# TF0060DCA.net
KiCad netlist of a schematic drawn in EAGLE
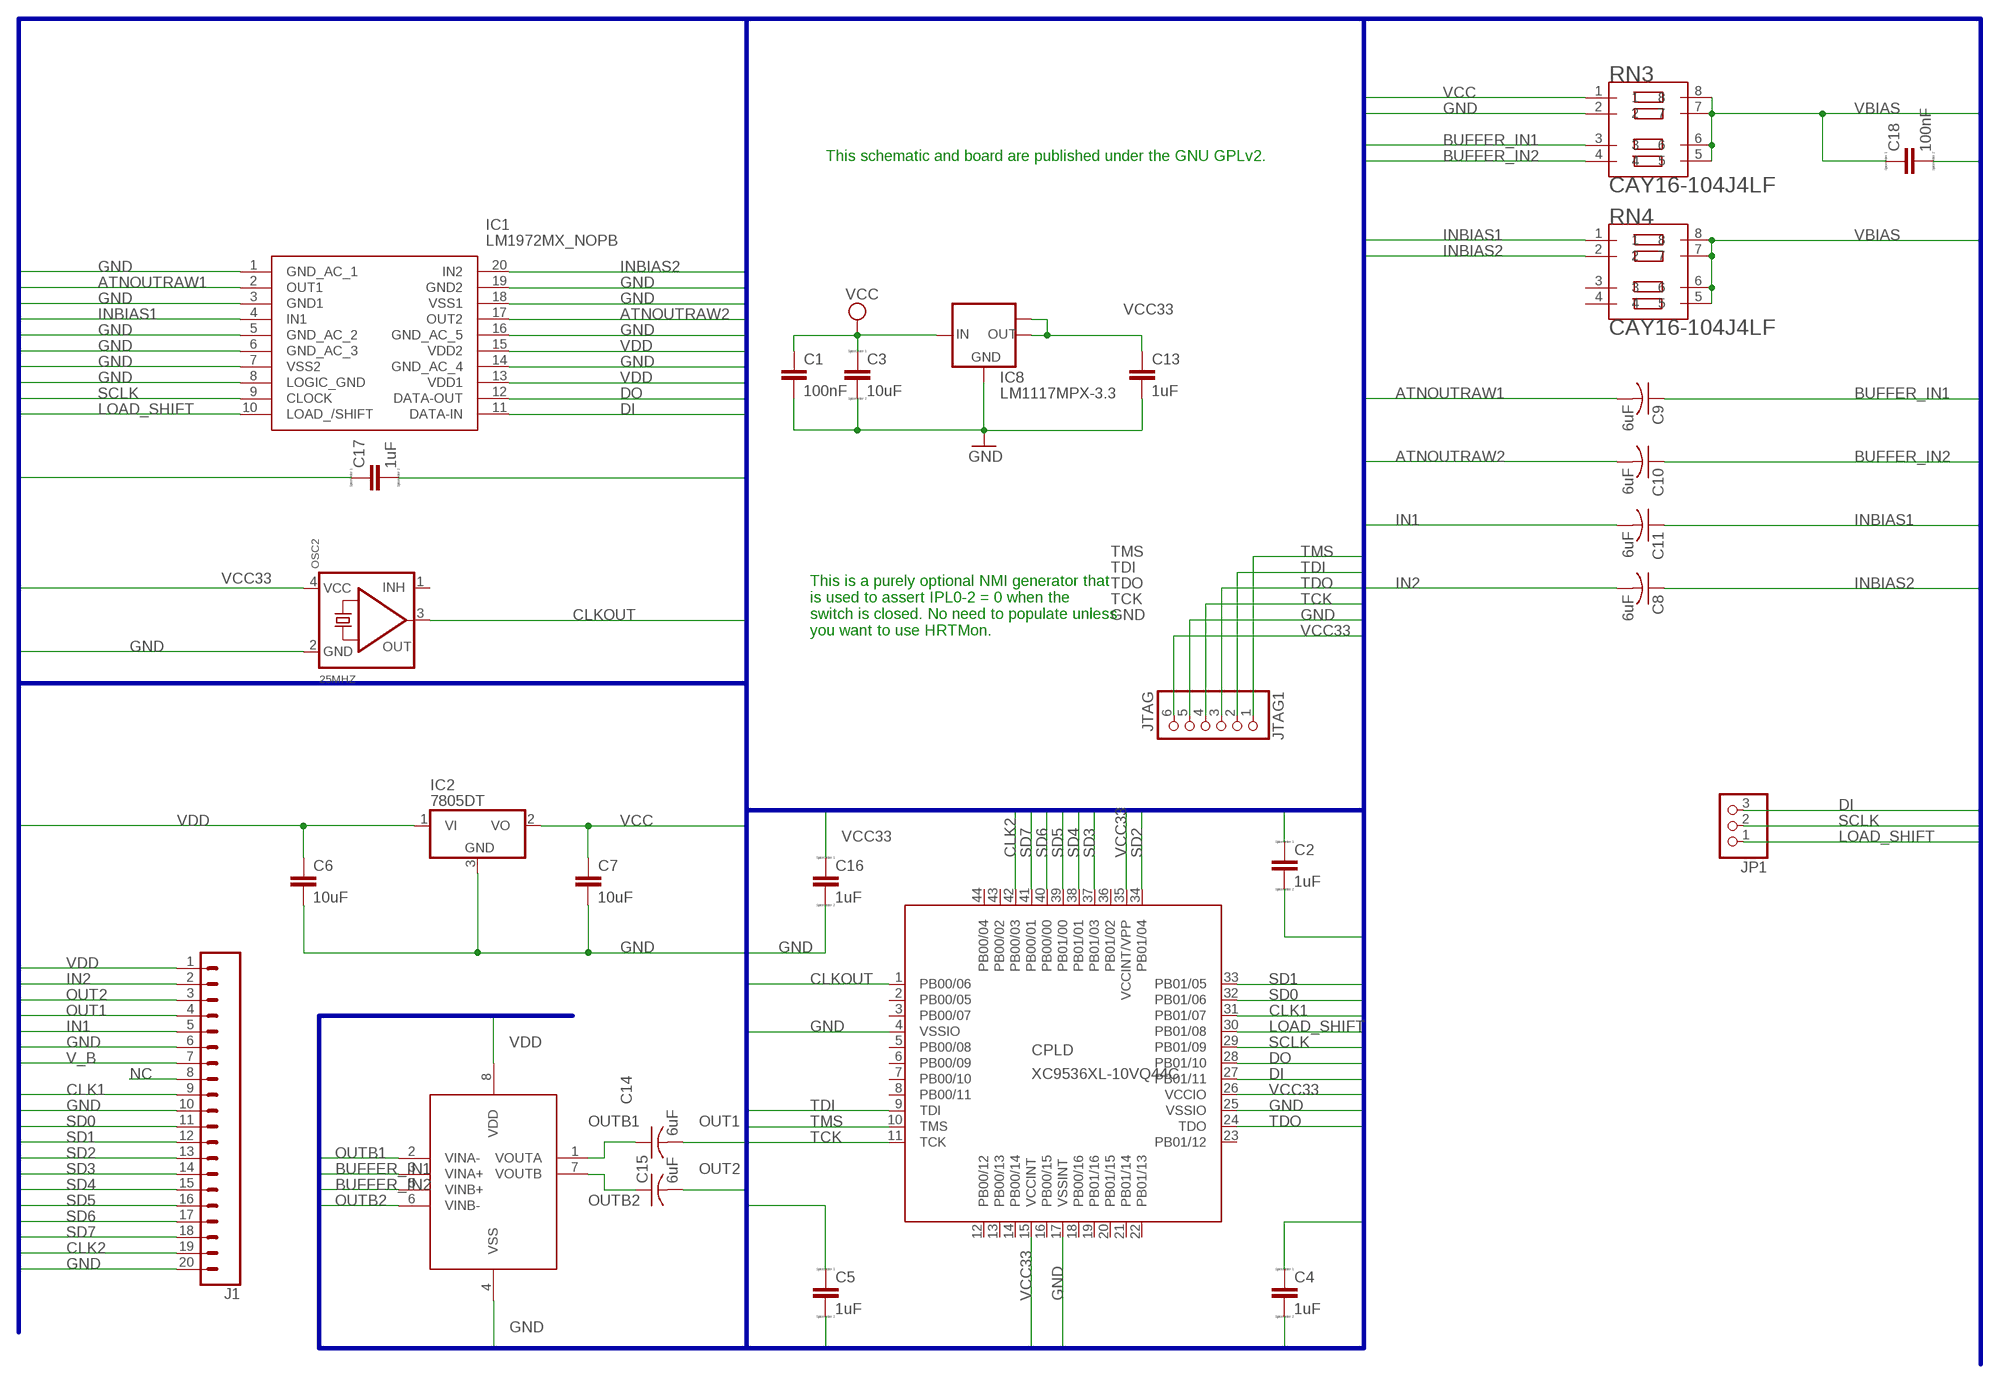
[diagram p0: schematic, sheet 1]

(export (version "E")
  (design (tool "Eeschema 10.0.6"))
  (components
    (comp (ref "C1")
      (value "100nF")
      (footprint "eagle-import:C1206")
      (libsource (lib "eagle-import") (part "C-EUC1206"))
    )
    (comp (ref "C2")
      (value "1uF")
      (footprint "eagle-import:C0603")
      (libsource (lib "eagle-import") (part "CC0603"))
    )
    (comp (ref "C3")
      (value "10uF")
      (footprint "eagle-import:C0603")
      (libsource (lib "eagle-import") (part "CC0603"))
    )
    (comp (ref "C4")
      (value "1uF")
      (footprint "eagle-import:C0603")
      (libsource (lib "eagle-import") (part "CC0603"))
    )
    (comp (ref "C5")
      (value "1uF")
      (footprint "eagle-import:C0603")
      (libsource (lib "eagle-import") (part "CC0603"))
    )
    (comp (ref "C6")
      (value "10uF")
      (footprint "eagle-import:C1206")
      (libsource (lib "eagle-import") (part "C-EUC1206"))
    )
    (comp (ref "C7")
      (value "10uF")
      (footprint "eagle-import:C1206")
      (libsource (lib "eagle-import") (part "C-EUC1206"))
    )
    (comp (ref "C8")
      (value "6uF")
      (footprint "eagle-import:C0805")
      (libsource (lib "eagle-import") (part "C-USC0805"))
    )
    (comp (ref "C9")
      (value "6uF")
      (footprint "eagle-import:C0805")
      (libsource (lib "eagle-import") (part "C-USC0805"))
    )
    (comp (ref "C10")
      (value "6uF")
      (footprint "eagle-import:C0805")
      (libsource (lib "eagle-import") (part "C-USC0805"))
    )
    (comp (ref "C11")
      (value "6uF")
      (footprint "eagle-import:C0805")
      (libsource (lib "eagle-import") (part "C-USC0805"))
    )
    (comp (ref "C13")
      (value "1uF")
      (footprint "eagle-import:C1206")
      (libsource (lib "eagle-import") (part "C-EUC1206"))
    )
    (comp (ref "C14")
      (value "6uF")
      (footprint "eagle-import:C0805")
      (libsource (lib "eagle-import") (part "C-USC0805"))
    )
    (comp (ref "C15")
      (value "6uF")
      (footprint "eagle-import:C0805")
      (libsource (lib "eagle-import") (part "C-USC0805"))
    )
    (comp (ref "C16")
      (value "1uF")
      (footprint "eagle-import:C0603")
      (libsource (lib "eagle-import") (part "CC0603"))
    )
    (comp (ref "C17")
      (value "1uF")
      (footprint "eagle-import:C0603")
      (libsource (lib "eagle-import") (part "CC0603"))
    )
    (comp (ref "C18")
      (value "100nF")
      (footprint "eagle-import:C0603")
      (libsource (lib "eagle-import") (part "CC0603"))
    )
    (comp (ref "CPLD")
      (value "XC9536XL-10VQ44C")
      (footprint "eagle-import:SQFP-S-10X10-44")
      (fields (field (name "MPN") "XC9536-15VQG44C"))
      (libsource (lib "eagle-import") (part "XC9536_44VQ"))
    )
    (comp (ref "IC1")
      (value "LM1972MX_NOPB")
      (footprint "eagle-import:SOIC127P1030X265-20N")
      (fields
        (field (name "MANUFACTURER_PART_NUMBER") "LM1972MX/NOPB")
        (field (name "MOUSER_PART_NUMBER") "926-LM1972MX/NOPB")
      )
      (libsource (lib "eagle-import") (part "LM1972MX_NOPB"))
    )
    (comp (ref "IC2")
      (value "7805DT")
      (footprint "eagle-import:TO252")
      (libsource (lib "eagle-import") (part "78DT05"))
    )
    (comp (ref "IC8")
      (value "LM1117MPX-3.3")
      (footprint "eagle-import:SOT223")
      (libsource (lib "eagle-import") (part "LM1117MPX-3.3"))
    )
    (comp (ref "IC12")
      (value "MCP6002T-I_SN")
      (footprint "eagle-import:SOIC127P600X175-8N")
      (fields
        (field (name "MANUFACTURER_PART_NUMBER") "MCP6002T-I/SN")
        (field (name "RS_PART_NUMBER") "8234276P")
      )
      (libsource (lib "eagle-import") (part "MCP6002T-I_SN"))
    )
    (comp (ref "J1")
      (value "CONN_20")
      (footprint "eagle-import:1X20")
      (libsource (lib "eagle-import") (part "CONN_20"))
    )
    (comp (ref "JP1")
      (value "PINHD-1X3")
      (footprint "eagle-import:1X03")
      (libsource (lib "eagle-import") (part "PINHD-1X3"))
    )
    (comp (ref "JTAG1")
      (value "JTAG")
      (footprint "eagle-import:1X06_ROUND")
      (libsource (lib "eagle-import") (part "HEADER-1X6ROUND"))
    )
    (comp (ref "OSC2")
      (value "25MHZ")
      (footprint "eagle-import:OSC_7X5MM")
      (libsource (lib "eagle-import") (part "OSCILLATOR"))
    )
    (comp (ref "RN3")
      (value "CAY16-104J4LF")
      (footprint "eagle-import:RESCAXE80P320X160-8N")
      (fields (field (name "MF") "Bourns") (field (name "MP") "CAY16-103J4LF"))
      (libsource (lib "eagle-import") (part "CAY16-103J4LF"))
    )
    (comp (ref "RN4")
      (value "CAY16-104J4LF")
      (footprint "eagle-import:RESCAXE80P320X160-8N")
      (fields (field (name "MF") "Bourns") (field (name "MP") "CAY16-103J4LF"))
      (libsource (lib "eagle-import") (part "CAY16-103J4LF"))
    )
  )
  (nets
    (net (code "1") (name "/ATNOUTRAW1") (class "Default")
      (node (ref "C9") (pin "2") (pinfunction "2_2") (pintype "passive"))
      (node (ref "IC1") (pin "2") (pinfunction "OUT1_2") (pintype "bidirectional"))
    )
    (net (code "2") (name "/ATNOUTRAW2") (class "Default")
      (node (ref "C10") (pin "2") (pinfunction "2_2") (pintype "passive"))
      (node (ref "IC1") (pin "17") (pinfunction "OUT2_17") (pintype "bidirectional"))
    )
    (net (code "3") (name "/BUFFER_IN1") (class "Default")
      (node (ref "C9") (pin "1") (pinfunction "1_1") (pintype "passive"))
      (node (ref "IC12") (pin "3") (pinfunction "VINA+_3") (pintype "bidirectional"))
      (node (ref "RN3") (pin "3") (pinfunction "3_3") (pintype "passive"))
    )
    (net (code "4") (name "/BUFFER_IN2") (class "Default")
      (node (ref "C10") (pin "1") (pinfunction "1_1") (pintype "passive"))
      (node (ref "IC12") (pin "5") (pinfunction "VINB+_5") (pintype "bidirectional"))
      (node (ref "RN3") (pin "4") (pinfunction "4_4") (pintype "passive"))
    )
    (net (code "5") (name "/CLK1") (class "Default")
      (node (ref "CPLD") (pin "31") (pinfunction "PB01/07_31") (pintype "bidirectional"))
      (node (ref "J1") (pin "9") (pinfunction "9_9") (pintype "passive"))
    )
    (net (code "6") (name "/CLK2") (class "Default")
      (node (ref "CPLD") (pin "42") (pinfunction "PB00/03_42") (pintype "bidirectional"))
      (node (ref "J1") (pin "19") (pinfunction "19_19") (pintype "passive"))
    )
    (net (code "7") (name "/CLKOUT") (class "Default")
      (node (ref "CPLD") (pin "1") (pinfunction "PB00/06_1") (pintype "bidirectional"))
      (node (ref "OSC2") (pin "3") (pinfunction "OUT_3") (pintype "output"))
    )
    (net (code "8") (name "/DI") (class "Default")
      (node (ref "CPLD") (pin "27") (pinfunction "PB01/11_27") (pintype "bidirectional"))
      (node (ref "IC1") (pin "11") (pinfunction "DATA-IN_11") (pintype "bidirectional"))
      (node (ref "JP1") (pin "3") (pinfunction "3_3") (pintype "passive"))
    )
    (net (code "9") (name "/DO") (class "Default")
      (node (ref "CPLD") (pin "28") (pinfunction "PB01/10_28") (pintype "bidirectional"))
      (node (ref "IC1") (pin "12") (pinfunction "DATA-OUT_12") (pintype "bidirectional"))
    )
    (net (code "10") (name "/IN1") (class "Default")
      (node (ref "C11") (pin "2") (pinfunction "2_2") (pintype "passive"))
      (node (ref "J1") (pin "5") (pinfunction "5_5") (pintype "passive"))
    )
    (net (code "11") (name "/IN2") (class "Default")
      (node (ref "C8") (pin "2") (pinfunction "2_2") (pintype "passive"))
      (node (ref "J1") (pin "2") (pinfunction "2_2") (pintype "passive"))
    )
    (net (code "12") (name "/INBIAS1") (class "Default")
      (node (ref "C11") (pin "1") (pinfunction "1_1") (pintype "passive"))
      (node (ref "IC1") (pin "4") (pinfunction "IN1_4") (pintype "bidirectional"))
      (node (ref "RN4") (pin "1") (pinfunction "1_1") (pintype "passive"))
    )
    (net (code "13") (name "/INBIAS2") (class "Default")
      (node (ref "C8") (pin "1") (pinfunction "1_1") (pintype "passive"))
      (node (ref "IC1") (pin "20") (pinfunction "IN2_20") (pintype "bidirectional"))
      (node (ref "RN4") (pin "2") (pinfunction "2_2") (pintype "passive"))
    )
    (net (code "14") (name "/LOAD_SHIFT") (class "Default")
      (node (ref "CPLD") (pin "30") (pinfunction "PB01/08_30") (pintype "bidirectional"))
      (node (ref "IC1") (pin "10") (pinfunction "LOAD_/SHIFT_10") (pintype "bidirectional"))
      (node (ref "JP1") (pin "1") (pinfunction "1_1") (pintype "passive"))
    )
    (net (code "15") (name "/NC") (class "Default")
      (node (ref "J1") (pin "8") (pinfunction "8_8") (pintype "passive"))
    )
    (net (code "16") (name "/OUT1") (class "Default")
      (node (ref "C14") (pin "2") (pinfunction "2_2") (pintype "passive"))
      (node (ref "J1") (pin "4") (pinfunction "4_4") (pintype "passive"))
    )
    (net (code "17") (name "/OUT2") (class "Default")
      (node (ref "C15") (pin "2") (pinfunction "2_2") (pintype "passive"))
      (node (ref "J1") (pin "3") (pinfunction "3_3") (pintype "passive"))
    )
    (net (code "18") (name "/OUTB1") (class "Default")
      (node (ref "C14") (pin "1") (pinfunction "1_1") (pintype "passive"))
      (node (ref "IC12") (pin "1") (pinfunction "VOUTA_1") (pintype "bidirectional"))
      (node (ref "IC12") (pin "2") (pinfunction "VINA-_2") (pintype "bidirectional"))
    )
    (net (code "19") (name "/OUTB2") (class "Default")
      (node (ref "C15") (pin "1") (pinfunction "1_1") (pintype "passive"))
      (node (ref "IC12") (pin "6") (pinfunction "VINB-_6") (pintype "bidirectional"))
      (node (ref "IC12") (pin "7") (pinfunction "VOUTB_7") (pintype "bidirectional"))
    )
    (net (code "20") (name "/SCLK") (class "Default")
      (node (ref "CPLD") (pin "29") (pinfunction "PB01/09_29") (pintype "bidirectional"))
      (node (ref "IC1") (pin "9") (pinfunction "CLOCK_9") (pintype "bidirectional"))
      (node (ref "JP1") (pin "2") (pinfunction "2_2") (pintype "passive"))
    )
    (net (code "21") (name "/SD0") (class "Default")
      (node (ref "CPLD") (pin "32") (pinfunction "PB01/06_32") (pintype "bidirectional"))
      (node (ref "J1") (pin "11") (pinfunction "11_11") (pintype "passive"))
    )
    (net (code "22") (name "/SD1") (class "Default")
      (node (ref "CPLD") (pin "33") (pinfunction "PB01/05_33") (pintype "bidirectional"))
      (node (ref "J1") (pin "12") (pinfunction "12_12") (pintype "passive"))
    )
    (net (code "23") (name "/SD2") (class "Default")
      (node (ref "CPLD") (pin "34") (pinfunction "PB01/04_34") (pintype "bidirectional"))
      (node (ref "J1") (pin "13") (pinfunction "13_13") (pintype "passive"))
    )
    (net (code "24") (name "/SD3") (class "Default")
      (node (ref "CPLD") (pin "37") (pinfunction "PB01/03_37") (pintype "bidirectional"))
      (node (ref "J1") (pin "14") (pinfunction "14_14") (pintype "passive"))
    )
    (net (code "25") (name "/SD4") (class "Default")
      (node (ref "CPLD") (pin "38") (pinfunction "PB01/01_38") (pintype "bidirectional"))
      (node (ref "J1") (pin "15") (pinfunction "15_15") (pintype "passive"))
    )
    (net (code "26") (name "/SD5") (class "Default")
      (node (ref "CPLD") (pin "39") (pinfunction "PB01/00_39") (pintype "bidirectional"))
      (node (ref "J1") (pin "16") (pinfunction "16_16") (pintype "passive"))
    )
    (net (code "27") (name "/SD6") (class "Default")
      (node (ref "CPLD") (pin "40") (pinfunction "PB00/00_40") (pintype "bidirectional"))
      (node (ref "J1") (pin "17") (pinfunction "17_17") (pintype "passive"))
    )
    (net (code "28") (name "/SD7") (class "Default")
      (node (ref "CPLD") (pin "41") (pinfunction "PB00/01_41") (pintype "bidirectional"))
      (node (ref "J1") (pin "18") (pinfunction "18_18") (pintype "passive"))
    )
    (net (code "29") (name "/TCK") (class "Default")
      (node (ref "CPLD") (pin "11") (pinfunction "TCK_11") (pintype "input"))
      (node (ref "JTAG1") (pin "4") (pinfunction "4_4") (pintype "passive"))
    )
    (net (code "30") (name "/TDI") (class "Default")
      (node (ref "CPLD") (pin "9") (pinfunction "TDI_9") (pintype "input"))
      (node (ref "JTAG1") (pin "2") (pinfunction "2_2") (pintype "passive"))
    )
    (net (code "31") (name "/TDO") (class "Default")
      (node (ref "CPLD") (pin "24") (pinfunction "TDO_24") (pintype "output"))
      (node (ref "JTAG1") (pin "3") (pinfunction "3_3") (pintype "passive"))
    )
    (net (code "32") (name "/TMS") (class "Default")
      (node (ref "CPLD") (pin "10") (pinfunction "TMS_10") (pintype "input"))
      (node (ref "JTAG1") (pin "1") (pinfunction "1_1") (pintype "passive"))
    )
    (net (code "33") (name "/VBIAS") (class "Default")
      (node (ref "C18") (pin "1") (pinfunction "1_1") (pintype "passive"))
      (node (ref "RN3") (pin "5") (pinfunction "5_5") (pintype "passive"))
      (node (ref "RN3") (pin "6") (pinfunction "6_6") (pintype "passive"))
      (node (ref "RN3") (pin "7") (pinfunction "7_7") (pintype "passive"))
      (node (ref "RN3") (pin "8") (pinfunction "8_8") (pintype "passive"))
      (node (ref "RN4") (pin "5") (pinfunction "5_5") (pintype "passive"))
      (node (ref "RN4") (pin "6") (pinfunction "6_6") (pintype "passive"))
      (node (ref "RN4") (pin "7") (pinfunction "7_7") (pintype "passive"))
      (node (ref "RN4") (pin "8") (pinfunction "8_8") (pintype "passive"))
    )
    (net (code "34") (name "/VCC33") (class "Default")
      (node (ref "C13") (pin "1") (pinfunction "1_1") (pintype "passive"))
      (node (ref "C16") (pin "1") (pinfunction "1_1") (pintype "passive"))
      (node (ref "C2") (pin "1") (pinfunction "1_1") (pintype "passive"))
      (node (ref "C4") (pin "1") (pinfunction "1_1") (pintype "passive"))
      (node (ref "C5") (pin "1") (pinfunction "1_1") (pintype "passive"))
      (node (ref "CPLD") (pin "15") (pinfunction "VCCINT_15") (pintype "power_in"))
      (node (ref "CPLD") (pin "26") (pinfunction "VCCIO_26") (pintype "power_in"))
      (node (ref "CPLD") (pin "35") (pinfunction "VCCINT/VPP_35") (pintype "input"))
      (node (ref "IC8") (pin "2") (pinfunction "OUT_2") (pintype "passive"))
      (node (ref "IC8") (pin "TAB") (pinfunction "OUT1_TAB") (pintype "passive"))
      (node (ref "JTAG1") (pin "6") (pinfunction "6_6") (pintype "passive"))
      (node (ref "OSC2") (pin "4") (pinfunction "VCC_4") (pintype "power_in"))
    )
    (net (code "35") (name "/VDD") (class "Default")
      (node (ref "C6") (pin "1") (pinfunction "1_1") (pintype "passive"))
      (node (ref "IC1") (pin "13") (pinfunction "VDD1_13") (pintype "bidirectional"))
      (node (ref "IC1") (pin "15") (pinfunction "VDD2_15") (pintype "bidirectional"))
      (node (ref "IC12") (pin "8") (pinfunction "VDD_8") (pintype "bidirectional"))
      (node (ref "IC2") (pin "1") (pinfunction "VI_1") (pintype "input"))
      (node (ref "J1") (pin "1") (pinfunction "1_1") (pintype "passive"))
    )
    (net (code "36") (name "/V_B") (class "Default")
      (node (ref "J1") (pin "7") (pinfunction "7_7") (pintype "passive"))
    )
    (net (code "37") (name "GND") (class "Default")
      (node (ref "C1") (pin "2") (pinfunction "2_2") (pintype "passive"))
      (node (ref "C13") (pin "2") (pinfunction "2_2") (pintype "passive"))
      (node (ref "C16") (pin "2") (pinfunction "2_2") (pintype "passive"))
      (node (ref "C17") (pin "2") (pinfunction "2_2") (pintype "passive"))
      (node (ref "C18") (pin "2") (pinfunction "2_2") (pintype "passive"))
      (node (ref "C2") (pin "2") (pinfunction "2_2") (pintype "passive"))
      (node (ref "C3") (pin "2") (pinfunction "2_2") (pintype "passive"))
      (node (ref "C4") (pin "2") (pinfunction "2_2") (pintype "passive"))
      (node (ref "C5") (pin "2") (pinfunction "2_2") (pintype "passive"))
      (node (ref "C6") (pin "2") (pinfunction "2_2") (pintype "passive"))
      (node (ref "C7") (pin "2") (pinfunction "2_2") (pintype "passive"))
      (node (ref "CPLD") (pin "17") (pinfunction "VSSINT_17") (pintype "power_in"))
      (node (ref "CPLD") (pin "25") (pinfunction "VSSIO_25") (pintype "power_in"))
      (node (ref "CPLD") (pin "4") (pinfunction "VSSIO_4") (pintype "power_in"))
      (node (ref "IC1") (pin "1") (pinfunction "GND_AC_1_1") (pintype "bidirectional"))
      (node (ref "IC1") (pin "14") (pinfunction "GND_AC_4_14") (pintype "bidirectional"))
      (node (ref "IC1") (pin "16") (pinfunction "GND_AC_5_16") (pintype "bidirectional"))
      (node (ref "IC1") (pin "18") (pinfunction "VSS1_18") (pintype "bidirectional"))
      (node (ref "IC1") (pin "19") (pinfunction "GND2_19") (pintype "bidirectional"))
      (node (ref "IC1") (pin "3") (pinfunction "GND1_3") (pintype "bidirectional"))
      (node (ref "IC1") (pin "5") (pinfunction "GND_AC_2_5") (pintype "bidirectional"))
      (node (ref "IC1") (pin "6") (pinfunction "GND_AC_3_6") (pintype "bidirectional"))
      (node (ref "IC1") (pin "7") (pinfunction "VSS2_7") (pintype "bidirectional"))
      (node (ref "IC1") (pin "8") (pinfunction "LOGIC_GND_8") (pintype "bidirectional"))
      (node (ref "IC12") (pin "4") (pinfunction "VSS_4") (pintype "bidirectional"))
      (node (ref "IC2") (pin "3") (pinfunction "GND_3") (pintype "passive"))
      (node (ref "IC8") (pin "1") (pinfunction "GND_1") (pintype "input"))
      (node (ref "J1") (pin "10") (pinfunction "10_10") (pintype "passive"))
      (node (ref "J1") (pin "20") (pinfunction "20_20") (pintype "passive"))
      (node (ref "J1") (pin "6") (pinfunction "6_6") (pintype "passive"))
      (node (ref "JTAG1") (pin "5") (pinfunction "5_5") (pintype "passive"))
      (node (ref "OSC2") (pin "2") (pinfunction "GND_2") (pintype "power_in"))
      (node (ref "RN3") (pin "2") (pinfunction "2_2") (pintype "passive"))
    )
    (net (code "38") (name "VCC") (class "Default")
      (node (ref "C1") (pin "1") (pinfunction "1_1") (pintype "passive"))
      (node (ref "C17") (pin "1") (pinfunction "1_1") (pintype "passive"))
      (node (ref "C3") (pin "1") (pinfunction "1_1") (pintype "passive"))
      (node (ref "C7") (pin "1") (pinfunction "1_1") (pintype "passive"))
      (node (ref "IC2") (pin "2") (pinfunction "VO_2") (pintype "passive"))
      (node (ref "IC8") (pin "3") (pinfunction "IN_3") (pintype "input"))
      (node (ref "RN3") (pin "1") (pinfunction "1_1") (pintype "passive"))
    )
    (net (code "39") (name "unconnected-(CPLD-PB00{slash}02-Pad43)") (class "Default")
      (node (ref "CPLD") (pin "43") (pinfunction "PB00/02_43") (pintype "bidirectional"))
    )
    (net (code "40") (name "unconnected-(CPLD-PB00{slash}04-Pad44)") (class "Default")
      (node (ref "CPLD") (pin "44") (pinfunction "PB00/04_44") (pintype "bidirectional"))
    )
    (net (code "41") (name "unconnected-(CPLD-PB00{slash}05-Pad2)") (class "Default")
      (node (ref "CPLD") (pin "2") (pinfunction "PB00/05_2") (pintype "bidirectional"))
    )
    (net (code "42") (name "unconnected-(CPLD-PB00{slash}07-Pad3)") (class "Default")
      (node (ref "CPLD") (pin "3") (pinfunction "PB00/07_3") (pintype "bidirectional"))
    )
    (net (code "43") (name "unconnected-(CPLD-PB00{slash}08-Pad5)") (class "Default")
      (node (ref "CPLD") (pin "5") (pinfunction "PB00/08_5") (pintype "bidirectional"))
    )
    (net (code "44") (name "unconnected-(CPLD-PB00{slash}09-Pad6)") (class "Default")
      (node (ref "CPLD") (pin "6") (pinfunction "PB00/09_6") (pintype "bidirectional"))
    )
    (net (code "45") (name "unconnected-(CPLD-PB00{slash}10-Pad7)") (class "Default")
      (node (ref "CPLD") (pin "7") (pinfunction "PB00/10_7") (pintype "bidirectional"))
    )
    (net (code "46") (name "unconnected-(CPLD-PB00{slash}11-Pad8)") (class "Default")
      (node (ref "CPLD") (pin "8") (pinfunction "PB00/11_8") (pintype "bidirectional"))
    )
    (net (code "47") (name "unconnected-(CPLD-PB00{slash}12-Pad12)") (class "Default")
      (node (ref "CPLD") (pin "12") (pinfunction "PB00/12_12") (pintype "bidirectional"))
    )
    (net (code "48") (name "unconnected-(CPLD-PB00{slash}13-Pad13)") (class "Default")
      (node (ref "CPLD") (pin "13") (pinfunction "PB00/13_13") (pintype "bidirectional"))
    )
    (net (code "49") (name "unconnected-(CPLD-PB00{slash}14-Pad14)") (class "Default")
      (node (ref "CPLD") (pin "14") (pinfunction "PB00/14_14") (pintype "bidirectional"))
    )
    (net (code "50") (name "unconnected-(CPLD-PB00{slash}15-Pad16)") (class "Default")
      (node (ref "CPLD") (pin "16") (pinfunction "PB00/15_16") (pintype "bidirectional"))
    )
    (net (code "51") (name "unconnected-(CPLD-PB00{slash}16-Pad18)") (class "Default")
      (node (ref "CPLD") (pin "18") (pinfunction "PB00/16_18") (pintype "bidirectional"))
    )
    (net (code "52") (name "unconnected-(CPLD-PB01{slash}02-Pad36)") (class "Default")
      (node (ref "CPLD") (pin "36") (pinfunction "PB01/02_36") (pintype "bidirectional"))
    )
    (net (code "53") (name "unconnected-(CPLD-PB01{slash}12-Pad23)") (class "Default")
      (node (ref "CPLD") (pin "23") (pinfunction "PB01/12_23") (pintype "bidirectional"))
    )
    (net (code "54") (name "unconnected-(CPLD-PB01{slash}13-Pad22)") (class "Default")
      (node (ref "CPLD") (pin "22") (pinfunction "PB01/13_22") (pintype "bidirectional"))
    )
    (net (code "55") (name "unconnected-(CPLD-PB01{slash}14-Pad21)") (class "Default")
      (node (ref "CPLD") (pin "21") (pinfunction "PB01/14_21") (pintype "bidirectional"))
    )
    (net (code "56") (name "unconnected-(CPLD-PB01{slash}15-Pad20)") (class "Default")
      (node (ref "CPLD") (pin "20") (pinfunction "PB01/15_20") (pintype "bidirectional"))
    )
    (net (code "57") (name "unconnected-(CPLD-PB01{slash}16-Pad19)") (class "Default")
      (node (ref "CPLD") (pin "19") (pinfunction "PB01/16_19") (pintype "bidirectional"))
    )
    (net (code "58") (name "unconnected-(OSC2-INH-Pad1)") (class "Default")
      (node (ref "OSC2") (pin "1") (pinfunction "INH_1") (pintype "bidirectional"))
    )
    (net (code "59") (name "unconnected-(RN4-Pad3)") (class "Default")
      (node (ref "RN4") (pin "3") (pinfunction "3_3") (pintype "passive"))
    )
    (net (code "60") (name "unconnected-(RN4-Pad4)") (class "Default")
      (node (ref "RN4") (pin "4") (pinfunction "4_4") (pintype "passive"))
    )
  )
)
